# Schematic_v1_0.net
KiCad netlist of a schematic drawn in EAGLE
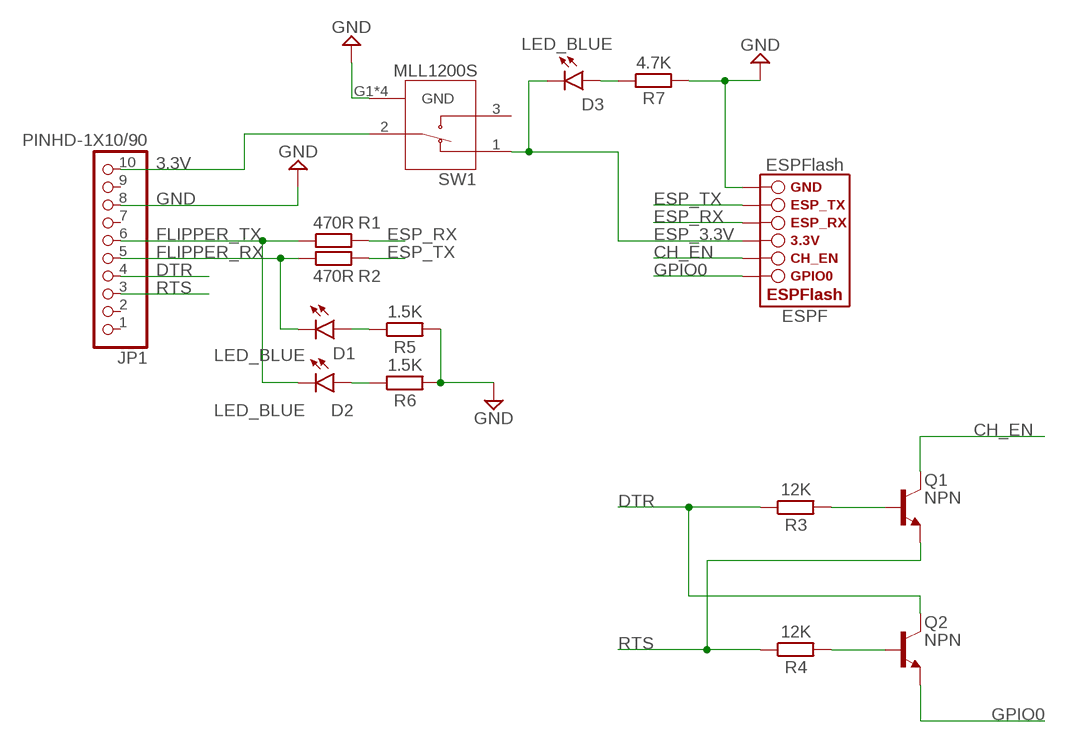
[diagram p0: schematic, sheet 1]

(export (version "E")
  (design (tool "Eeschema 10.0.6"))
  (components
    (comp (ref "D1")
      (value "LED_BLUE")
      (footprint "eagle-import:LEDC1608X55N_FLAT-B")
      (libsource (lib "eagle-import") (part "CHIP-FLAT-B_0603-0.55MM"))
    )
    (comp (ref "D2")
      (value "LED_BLUE")
      (footprint "eagle-import:LEDC1608X55N_FLAT-B")
      (libsource (lib "eagle-import") (part "CHIP-FLAT-B_0603-0.55MM"))
    )
    (comp (ref "D3")
      (value "LED_BLUE")
      (footprint "eagle-import:LEDC1608X55N_FLAT-B")
      (libsource (lib "eagle-import") (part "CHIP-FLAT-B_0603-0.55MM"))
    )
    (comp (ref "ESPF")
      (value "ESPFLASH-1X6-2.54-PLAIN")
      (footprint "eagle-import:1X6-2.54-PLAIN")
      (libsource (lib "eagle-import") (part "ESPFLASH-1X6-2.54-PLAIN"))
    )
    (comp (ref "JP1")
      (value "PINHD-1X10/90")
      (footprint "eagle-import:1X10_90")
      (libsource (lib "eagle-import") (part "PINHD-1X10/90"))
    )
    (comp (ref "Q1")
      (value "NPN")
      (footprint "eagle-import:SOT95P237X112-3N")
      (libsource (lib "eagle-import") (part "NPNSOT23-BEC_"))
    )
    (comp (ref "Q2")
      (value "NPN")
      (footprint "eagle-import:SOT95P237X112-3N")
      (libsource (lib "eagle-import") (part "NPNSOT23-BEC_"))
    )
    (comp (ref "R1")
      (value "470R")
      (footprint "eagle-import:RESC1608X60")
      (libsource (lib "eagle-import") (part "RCHIP-0603(1608-METRIC)_"))
    )
    (comp (ref "R2")
      (value "470R")
      (footprint "eagle-import:RESC1608X60")
      (libsource (lib "eagle-import") (part "RCHIP-0603(1608-METRIC)_"))
    )
    (comp (ref "R3")
      (value "12K")
      (footprint "eagle-import:RESC1608X60")
      (libsource (lib "eagle-import") (part "RCHIP-0603(1608-METRIC)_"))
    )
    (comp (ref "R4")
      (value "12K")
      (footprint "eagle-import:RESC1608X60")
      (libsource (lib "eagle-import") (part "RCHIP-0603(1608-METRIC)_"))
    )
    (comp (ref "R5")
      (value "1.5K")
      (footprint "eagle-import:RESC1608X60")
      (libsource (lib "eagle-import") (part "RCHIP-0603(1608-METRIC)_"))
    )
    (comp (ref "R6")
      (value "1.5K")
      (footprint "eagle-import:RESC1608X60")
      (libsource (lib "eagle-import") (part "RCHIP-0603(1608-METRIC)_"))
    )
    (comp (ref "R7")
      (value "4.7K")
      (footprint "eagle-import:RESC1608X60")
      (libsource (lib "eagle-import") (part "RCHIP-0603(1608-METRIC)_"))
    )
    (comp (ref "SW1")
      (value "MLL1200S")
      (footprint "eagle-import:SW_MLL1200S")
      (fields (field (name "COMMENT") "1437575-1"))
      (libsource (lib "eagle-import") (part "MLL1200S"))
    )
  )
  (nets
    (net (code "1") (name "/3.3V") (class "Default")
      (node (ref "JP1") (pin "10") (pinfunction "10_10") (pintype "passive"))
      (node (ref "SW1") (pin "2") (pinfunction "2_2") (pintype "passive"))
    )
    (net (code "2") (name "/CH_EN") (class "Default")
      (node (ref "ESPF") (pin "5") (pinfunction "CH_EN_5") (pintype "passive"))
      (node (ref "Q1") (pin "3") (pinfunction "C_3") (pintype "passive"))
    )
    (net (code "3") (name "/DTR") (class "Default")
      (node (ref "JP1") (pin "4") (pinfunction "4_4") (pintype "passive"))
      (node (ref "Q2") (pin "3") (pinfunction "C_3") (pintype "passive"))
      (node (ref "R3") (pin "1") (pinfunction "1_1") (pintype "passive"))
    )
    (net (code "4") (name "/ESP_3.3V") (class "Default")
      (node (ref "D3") (pin "C") (pinfunction "C_C") (pintype "passive"))
      (node (ref "ESPF") (pin "4") (pinfunction "3.3V_4") (pintype "passive"))
      (node (ref "SW1") (pin "1") (pinfunction "1_1") (pintype "passive"))
    )
    (net (code "5") (name "/ESP_RX") (class "Default")
      (node (ref "ESPF") (pin "3") (pinfunction "ESP_RX_3") (pintype "passive"))
      (node (ref "R1") (pin "2") (pinfunction "2_2") (pintype "passive"))
    )
    (net (code "6") (name "/ESP_TX") (class "Default")
      (node (ref "ESPF") (pin "2") (pinfunction "ESP_TX_2") (pintype "passive"))
      (node (ref "R2") (pin "2") (pinfunction "2_2") (pintype "passive"))
    )
    (net (code "7") (name "/FLIPPER_RX") (class "Default")
      (node (ref "D1") (pin "C") (pinfunction "C_C") (pintype "passive"))
      (node (ref "JP1") (pin "5") (pinfunction "5_5") (pintype "passive"))
      (node (ref "R2") (pin "1") (pinfunction "1_1") (pintype "passive"))
    )
    (net (code "8") (name "/FLIPPER_TX") (class "Default")
      (node (ref "D2") (pin "C") (pinfunction "C_C") (pintype "passive"))
      (node (ref "JP1") (pin "6") (pinfunction "6_6") (pintype "passive"))
      (node (ref "R1") (pin "1") (pinfunction "1_1") (pintype "passive"))
    )
    (net (code "9") (name "/GPIO0") (class "Default")
      (node (ref "ESPF") (pin "6") (pinfunction "GPIO0_6") (pintype "passive"))
      (node (ref "Q2") (pin "2") (pinfunction "E_2") (pintype "passive"))
    )
    (net (code "10") (name "/RTS") (class "Default")
      (node (ref "JP1") (pin "3") (pinfunction "3_3") (pintype "passive"))
      (node (ref "Q1") (pin "2") (pinfunction "E_2") (pintype "passive"))
      (node (ref "R4") (pin "1") (pinfunction "1_1") (pintype "passive"))
    )
    (net (code "11") (name "GND") (class "Default")
      (node (ref "ESPF") (pin "1") (pinfunction "GND_1") (pintype "passive"))
      (node (ref "JP1") (pin "8") (pinfunction "8_8") (pintype "passive"))
      (node (ref "R5") (pin "2") (pinfunction "2_2") (pintype "passive"))
      (node (ref "R6") (pin "2") (pinfunction "2_2") (pintype "passive"))
      (node (ref "R7") (pin "2") (pinfunction "2_2") (pintype "passive"))
      (node (ref "SW1") (pin "G1") (pinfunction "GND_G1") (pintype "power_in"))
      (node (ref "SW1") (pin "G2") (pinfunction "GND_G2") (pintype "power_in"))
      (node (ref "SW1") (pin "G3") (pinfunction "GND_G3") (pintype "power_in"))
      (node (ref "SW1") (pin "G4") (pinfunction "GND_G4") (pintype "power_in"))
    )
    (net (code "12") (name "Net-(D1-PadA)") (class "Default")
      (node (ref "D1") (pin "A") (pinfunction "A_A") (pintype "passive"))
      (node (ref "R5") (pin "1") (pinfunction "1_1") (pintype "passive"))
    )
    (net (code "13") (name "Net-(D2-PadA)") (class "Default")
      (node (ref "D2") (pin "A") (pinfunction "A_A") (pintype "passive"))
      (node (ref "R6") (pin "1") (pinfunction "1_1") (pintype "passive"))
    )
    (net (code "14") (name "Net-(D3-PadA)") (class "Default")
      (node (ref "D3") (pin "A") (pinfunction "A_A") (pintype "passive"))
      (node (ref "R7") (pin "1") (pinfunction "1_1") (pintype "passive"))
    )
    (net (code "15") (name "Net-(Q1-B)") (class "Default")
      (node (ref "Q1") (pin "1") (pinfunction "B_1") (pintype "passive"))
      (node (ref "R3") (pin "2") (pinfunction "2_2") (pintype "passive"))
    )
    (net (code "16") (name "Net-(Q2-B)") (class "Default")
      (node (ref "Q2") (pin "1") (pinfunction "B_1") (pintype "passive"))
      (node (ref "R4") (pin "2") (pinfunction "2_2") (pintype "passive"))
    )
    (net (code "17") (name "unconnected-(JP1-Pad1)") (class "Default")
      (node (ref "JP1") (pin "1") (pinfunction "1_1") (pintype "passive"))
    )
    (net (code "18") (name "unconnected-(JP1-Pad2)") (class "Default")
      (node (ref "JP1") (pin "2") (pinfunction "2_2") (pintype "passive"))
    )
    (net (code "19") (name "unconnected-(JP1-Pad7)") (class "Default")
      (node (ref "JP1") (pin "7") (pinfunction "7_7") (pintype "passive"))
    )
    (net (code "20") (name "unconnected-(JP1-Pad9)") (class "Default")
      (node (ref "JP1") (pin "9") (pinfunction "9_9") (pintype "passive"))
    )
    (net (code "21") (name "unconnected-(SW1-Pad3)") (class "Default")
      (node (ref "SW1") (pin "3") (pinfunction "3_3") (pintype "passive"))
    )
  )
)
